# 4P_JST-PH-3_EXT.net
KiCad netlist of a schematic drawn in Altium Designer
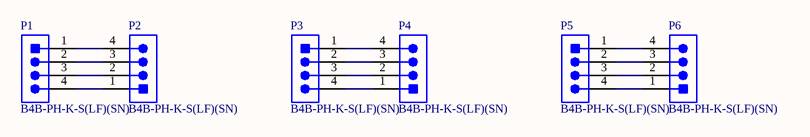
[diagram p0: 4P_JST-PH-3_EXT.SchDoc]

(export (version "E")
  (design (tool "Eeschema 10.0.6"))
  (components
    (comp (ref "P1")
      (value "B4B-PH-K-S(LF)(SN)")
      (footprint "JST-B4B-PH-K-S_V")
      (fields (field (name "MANUFACTURER") "JST"))
      (libsource (lib "Altium Content Vault") (part "CN-1P-M-R4"))
    )
    (comp (ref "P2")
      (value "B4B-PH-K-S(LF)(SN)")
      (footprint "JST-B4B-PH-K-S_V")
      (fields (field (name "MANUFACTURER") "JST"))
      (libsource (lib "") (part "CN-1P-M-R4_1"))
    )
    (comp (ref "P3")
      (value "B4B-PH-K-S(LF)(SN)")
      (footprint "JST-B4B-PH-K-S_V")
      (fields (field (name "MANUFACTURER") "JST"))
      (libsource (lib "Altium Content Vault") (part "CN-1P-M-R4"))
    )
    (comp (ref "P4")
      (value "B4B-PH-K-S(LF)(SN)")
      (footprint "JST-B4B-PH-K-S_V")
      (fields (field (name "MANUFACTURER") "JST"))
      (libsource (lib "") (part "CN-1P-M-R4_1"))
    )
    (comp (ref "P5")
      (value "B4B-PH-K-S(LF)(SN)")
      (footprint "JST-B4B-PH-K-S_V")
      (fields (field (name "MANUFACTURER") "JST"))
      (libsource (lib "Altium Content Vault") (part "CN-1P-M-R4"))
    )
    (comp (ref "P6")
      (value "B4B-PH-K-S(LF)(SN)")
      (footprint "JST-B4B-PH-K-S_V")
      (fields (field (name "MANUFACTURER") "JST"))
      (libsource (lib "") (part "CN-1P-M-R4_1"))
    )
  )
  (nets
    (net (code "1") (name "Net-(P1-Pad1)") (class "Default")
      (node (ref "P1") (pin "1") (pinfunction "1_1") (pintype "passive"))
      (node (ref "P2") (pin "4") (pinfunction "4_4") (pintype "passive"))
    )
    (net (code "2") (name "Net-(P1-Pad2)") (class "Default")
      (node (ref "P1") (pin "2") (pinfunction "2_2") (pintype "passive"))
      (node (ref "P2") (pin "3") (pinfunction "3_3") (pintype "passive"))
    )
    (net (code "3") (name "Net-(P1-Pad3)") (class "Default")
      (node (ref "P1") (pin "3") (pinfunction "3_3") (pintype "passive"))
      (node (ref "P2") (pin "2") (pinfunction "2_2") (pintype "passive"))
    )
    (net (code "4") (name "Net-(P1-Pad4)") (class "Default")
      (node (ref "P1") (pin "4") (pinfunction "4_4") (pintype "passive"))
      (node (ref "P2") (pin "1") (pinfunction "1_1") (pintype "passive"))
    )
    (net (code "5") (name "Net-(P3-Pad1)") (class "Default")
      (node (ref "P3") (pin "1") (pinfunction "1_1") (pintype "passive"))
      (node (ref "P4") (pin "4") (pinfunction "4_4") (pintype "passive"))
    )
    (net (code "6") (name "Net-(P3-Pad2)") (class "Default")
      (node (ref "P3") (pin "2") (pinfunction "2_2") (pintype "passive"))
      (node (ref "P4") (pin "3") (pinfunction "3_3") (pintype "passive"))
    )
    (net (code "7") (name "Net-(P3-Pad3)") (class "Default")
      (node (ref "P3") (pin "3") (pinfunction "3_3") (pintype "passive"))
      (node (ref "P4") (pin "2") (pinfunction "2_2") (pintype "passive"))
    )
    (net (code "8") (name "Net-(P3-Pad4)") (class "Default")
      (node (ref "P3") (pin "4") (pinfunction "4_4") (pintype "passive"))
      (node (ref "P4") (pin "1") (pinfunction "1_1") (pintype "passive"))
    )
    (net (code "9") (name "Net-(P5-Pad1)") (class "Default")
      (node (ref "P5") (pin "1") (pinfunction "1_1") (pintype "passive"))
      (node (ref "P6") (pin "4") (pinfunction "4_4") (pintype "passive"))
    )
    (net (code "10") (name "Net-(P5-Pad2)") (class "Default")
      (node (ref "P5") (pin "2") (pinfunction "2_2") (pintype "passive"))
      (node (ref "P6") (pin "3") (pinfunction "3_3") (pintype "passive"))
    )
    (net (code "11") (name "Net-(P5-Pad3)") (class "Default")
      (node (ref "P5") (pin "3") (pinfunction "3_3") (pintype "passive"))
      (node (ref "P6") (pin "2") (pinfunction "2_2") (pintype "passive"))
    )
    (net (code "12") (name "Net-(P5-Pad4)") (class "Default")
      (node (ref "P5") (pin "4") (pinfunction "4_4") (pintype "passive"))
      (node (ref "P6") (pin "1") (pinfunction "1_1") (pintype "passive"))
    )
  )
)
